# battery_charger.net
KiCad netlist of a schematic drawn in Altium Designer
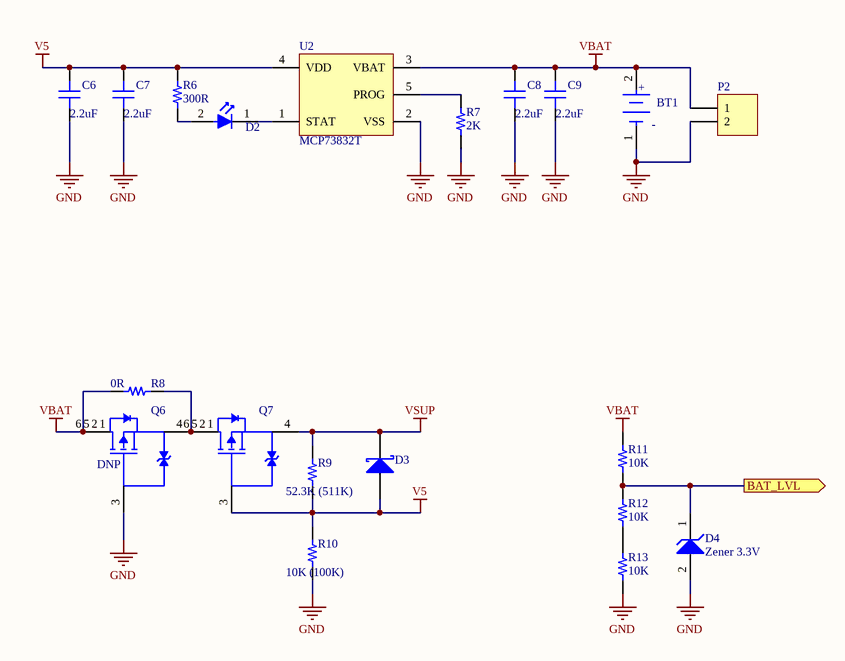
[diagram p0: battery_charger.SchDoc]

(export (version "E")
  (design (tool "Eeschema 10.0.6"))
  (components
    (comp (ref "BT1")
      (value "18650_battery_holder")
      (footprint "Keystone_1043_0")
      (description "Batt Holder 18650 1 Cell")
      (libsource (lib "BatteryHolder") (part "18650_battery_holder"))
    )
    (comp (ref "C6")
      (value "2.2uF")
      (footprint "CAP 0603_1608")
      (description "SMT Capacitor")
      (fields (field (name "MF") "Samsung") (field (name "MP") "CL10A225KP8NNNC"))
      (libsource (lib "Capacitor") (part "Capacitor"))
    )
    (comp (ref "C7")
      (value "2.2uF")
      (footprint "CAP 0603_1608")
      (description "SMT Capacitor")
      (fields (field (name "MF") "Samsung") (field (name "MP") "CL10A225KP8NNNC"))
      (libsource (lib "Capacitor") (part "Capacitor"))
    )
    (comp (ref "C8")
      (value "2.2uF")
      (footprint "CAP 0603_1608")
      (description "SMT Capacitor")
      (fields (field (name "MF") "Samsung") (field (name "MP") "CL10A225KP8NNNC"))
      (libsource (lib "Capacitor") (part "Capacitor"))
    )
    (comp (ref "C9")
      (value "2.2uF")
      (footprint "CAP 0603_1608")
      (description "SMT Capacitor")
      (fields (field (name "MF") "Samsung") (field (name "MP") "CL10A225KP8NNNC"))
      (libsource (lib "Capacitor") (part "Capacitor"))
    )
    (comp (ref "D2")
      (value "Red")
      (footprint "Würth_Elektronik_0_MFG")
      (description "Led Diffused SMD")
      (fields (field (name "MF") "LiteOn") (field (name "MP") "LTST-C190KRKT"))
      (libsource (lib "Diode") (part "LED SMD"))
    )
    (comp (ref "D3")
      (value "*")
      (footprint "Rohm_TUMD2M_MFG")
      (fields (field (name "MF") "Toshiba") (field (name "MP") "CUHS20F30,H3F"))
      (libsource (lib "Diode") (part "Schottky Diode"))
    )
    (comp (ref "D4")
      (value "Zener 3.3V")
      (footprint "Diodes_SOD-123_0")
      (description "Zener Voltage Regulator")
      (fields (field (name "MANUFACTURER") "On Semiconductor") (field (name "MF") "Onsemi"))
      (libsource (lib "Diode") (part "Zener Diode"))
    )
    (comp (ref "P2")
      (value "DNP")
      (footprint "HDR1X2")
      (description "Header, 2-Pin")
      (fields (field (name "PUBLISHER") "Altium Limited"))
      (libsource (lib "Connector") (part "Header 2"))
    )
    (comp (ref "Q6")
      (value "DNP")
      (footprint "Diodes_Inc._TSOT26_MFG")
      (description "P-Channel Enhancement Mode MOS Transistor, 3-Pin SOT23")
      (fields (field (name "MF") "Vishay") (field (name "MP") "SI3421DV-T1-GE3"))
      (libsource (lib "Mosfet") (part "Mosfet-P-6_ESD"))
    )
    (comp (ref "Q7")
      (value "P Mosfet")
      (footprint "Diodes_Inc._TSOT26_MFG")
      (description "P-Channel Enhancement Mode MOS Transistor, 3-Pin SOT23")
      (fields (field (name "MF") "Vishay") (field (name "MP") "SI3421DV-T1-GE3"))
      (libsource (lib "Mosfet") (part "Mosfet-P-6_ESD"))
    )
    (comp (ref "R6")
      (value "300R")
      (footprint "RES 0603_1608")
      (description "SMT Resistor")
      (fields (field (name "MF") "YAGEO") (field (name "MP") "AC0603FR-07300RL"))
      (libsource (lib "Resistor") (part "Resistor"))
    )
    (comp (ref "R7")
      (value "2K")
      (footprint "RES 0603_1608")
      (description "SMT Resistor")
      (fields (field (name "MF") "YAGEO") (field (name "MP") "AC0603FR-072KL"))
      (libsource (lib "Resistor") (part "Resistor"))
    )
    (comp (ref "R8")
      (value "0R")
      (footprint "RES 0603_1608")
      (description "SMT Resistor")
      (fields (field (name "MF") "YAGEO") (field (name "MP") "AC0603FR-070RL"))
      (libsource (lib "Resistor") (part "Resistor"))
    )
    (comp (ref "R9")
      (value "52.3K (511K)")
      (footprint "RES 0603_1608")
      (description "SMT Resistor")
      (fields (field (name "MF") "YAGEO") (field (name "MP") "AC0603FR-0752K3L"))
      (libsource (lib "Resistor") (part "Resistor"))
    )
    (comp (ref "R10")
      (value "10K (100K)")
      (footprint "RES 0603_1608")
      (description "SMT Resistor")
      (fields (field (name "MF") "YAGEO") (field (name "MP") "AC0603FR-0710KL"))
      (libsource (lib "Resistor") (part "Resistor"))
    )
    (comp (ref "R11")
      (value "10K")
      (footprint "RES 0603_1608")
      (description "SMT Resistor")
      (fields (field (name "MF") "YAGEO") (field (name "MP") "AC0603FR-0710KL"))
      (libsource (lib "Resistor") (part "Resistor"))
    )
    (comp (ref "R12")
      (value "10K")
      (footprint "RES 0603_1608")
      (description "SMT Resistor")
      (fields (field (name "MF") "YAGEO") (field (name "MP") "AC0603FR-0710KL"))
      (libsource (lib "Resistor") (part "Resistor"))
    )
    (comp (ref "R13")
      (value "10K")
      (footprint "RES 0603_1608")
      (description "SMT Resistor")
      (fields (field (name "MF") "YAGEO") (field (name "MP") "AC0603FR-0710KL"))
      (libsource (lib "Resistor") (part "Resistor"))
    )
    (comp (ref "U2")
      (value "MCP73832T")
      (footprint "MICROCHIP SOT-23-5 OT")
      (fields (field (name "PARTNUMBER") "MCP73832T-2DCI/OT") (field (name "MF") "Microchip"))
      (libsource (lib "BatteryManagers") (part "MCP73832T"))
    )
  )
  (nets
    (net (code "1") (name "/BAT_LVL") (class "Default")
      (node (ref "D4") (pin "1") (pinfunction "K_1") (pintype "passive"))
      (node (ref "R11") (pin "2") (pinfunction "2_2") (pintype "passive"))
      (node (ref "R12") (pin "1") (pinfunction "1_1") (pintype "passive"))
    )
    (net (code "2") (name "GND") (class "Default")
      (node (ref "BT1") (pin "1") (pinfunction "C_1") (pintype "passive"))
      (node (ref "C6") (pin "2") (pinfunction "2_2") (pintype "passive"))
      (node (ref "C7") (pin "2") (pinfunction "2_2") (pintype "passive"))
      (node (ref "C8") (pin "2") (pinfunction "2_2") (pintype "passive"))
      (node (ref "C9") (pin "2") (pinfunction "2_2") (pintype "passive"))
      (node (ref "D4") (pin "2") (pinfunction "A_2") (pintype "passive"))
      (node (ref "P2") (pin "2") (pinfunction "2_2") (pintype "passive"))
      (node (ref "Q6") (pin "3") (pinfunction "G_3") (pintype "passive"))
      (node (ref "R10") (pin "2") (pinfunction "2_2") (pintype "passive"))
      (node (ref "R13") (pin "2") (pinfunction "2_2") (pintype "passive"))
      (node (ref "R7") (pin "2") (pinfunction "2_2") (pintype "passive"))
      (node (ref "U2") (pin "2") (pinfunction "VSS_2") (pintype "power_in"))
    )
    (net (code "3") (name "Net-(D2-A)") (class "Default")
      (node (ref "D2") (pin "2") (pinfunction "A_2") (pintype "passive"))
      (node (ref "R6") (pin "1") (pinfunction "1_1") (pintype "passive"))
    )
    (net (code "4") (name "Net-(D2-C)") (class "Default")
      (node (ref "D2") (pin "1") (pinfunction "C_1") (pintype "passive"))
      (node (ref "U2") (pin "1") (pinfunction "STAT_1") (pintype "open_collector"))
    )
    (net (code "5") (name "Net-(Q6-S)") (class "Default")
      (node (ref "Q6") (pin "4") (pinfunction "S_4") (pintype "passive"))
      (node (ref "Q7") (pin "1") (pinfunction "D_1") (pintype "passive"))
      (node (ref "Q7") (pin "2") (pinfunction "D_2") (pintype "passive"))
      (node (ref "Q7") (pin "5") (pinfunction "D_5") (pintype "passive"))
      (node (ref "Q7") (pin "6") (pinfunction "D_6") (pintype "passive"))
      (node (ref "R8") (pin "2") (pinfunction "2_2") (pintype "passive"))
    )
    (net (code "6") (name "Net-(R12-Pad2)") (class "Default")
      (node (ref "R12") (pin "2") (pinfunction "2_2") (pintype "passive"))
      (node (ref "R13") (pin "1") (pinfunction "1_1") (pintype "passive"))
    )
    (net (code "7") (name "Net-(U2-PROG)") (class "Default")
      (node (ref "R7") (pin "1") (pinfunction "1_1") (pintype "passive"))
      (node (ref "U2") (pin "5") (pinfunction "PROG_5") (pintype "passive"))
    )
    (net (code "8") (name "V5") (class "Default")
      (node (ref "C6") (pin "1") (pinfunction "1_1") (pintype "passive"))
      (node (ref "C7") (pin "1") (pinfunction "1_1") (pintype "passive"))
      (node (ref "D3") (pin "2") (pinfunction "A_2") (pintype "passive"))
      (node (ref "Q7") (pin "3") (pinfunction "G_3") (pintype "passive"))
      (node (ref "R10") (pin "1") (pinfunction "1_1") (pintype "passive"))
      (node (ref "R6") (pin "2") (pinfunction "2_2") (pintype "passive"))
      (node (ref "R9") (pin "2") (pinfunction "2_2") (pintype "passive"))
      (node (ref "U2") (pin "4") (pinfunction "VDD_4") (pintype "power_in"))
    )
    (net (code "9") (name "VBAT") (class "Default")
      (node (ref "BT1") (pin "2") (pinfunction "A_2") (pintype "passive"))
      (node (ref "C8") (pin "1") (pinfunction "1_1") (pintype "passive"))
      (node (ref "C9") (pin "1") (pinfunction "1_1") (pintype "passive"))
      (node (ref "P2") (pin "1") (pinfunction "1_1") (pintype "passive"))
      (node (ref "Q6") (pin "1") (pinfunction "D_1") (pintype "passive"))
      (node (ref "Q6") (pin "2") (pinfunction "D_2") (pintype "passive"))
      (node (ref "Q6") (pin "5") (pinfunction "D_5") (pintype "passive"))
      (node (ref "Q6") (pin "6") (pinfunction "D_6") (pintype "passive"))
      (node (ref "R11") (pin "1") (pinfunction "1_1") (pintype "passive"))
      (node (ref "R8") (pin "1") (pinfunction "1_1") (pintype "passive"))
      (node (ref "U2") (pin "3") (pinfunction "VBAT_3") (pintype "power_in"))
    )
    (net (code "10") (name "VSUP") (class "Default")
      (node (ref "D3") (pin "1") (pinfunction "K_1") (pintype "passive"))
      (node (ref "Q7") (pin "4") (pinfunction "S_4") (pintype "passive"))
      (node (ref "R9") (pin "1") (pinfunction "1_1") (pintype "passive"))
    )
  )
)
